# TripleAttenumixer.net
KiCad netlist of a schematic drawn in EAGLE
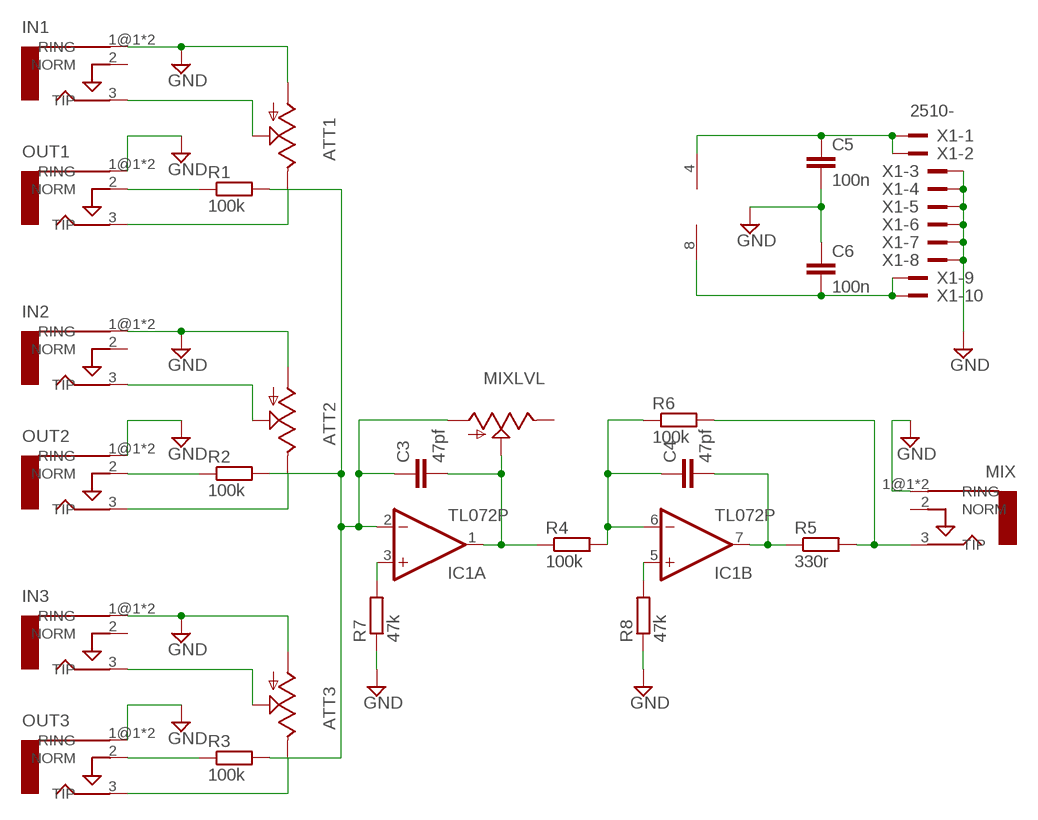
[diagram p0: schematic, sheet 1]

(export (version "E")
  (design (tool "Eeschema 10.0.6"))
  (components
    (comp (ref "ATT1")
      (value "US-EVUF2A")
      (footprint "eagle-import:EVUF")
      (libsource (lib "eagle-import") (part "US-EVUAF2"))
    )
    (comp (ref "ATT2")
      (value "US-EVUF2A")
      (footprint "eagle-import:EVUF")
      (libsource (lib "eagle-import") (part "US-EVUAF2"))
    )
    (comp (ref "ATT3")
      (value "US-EVUF2A")
      (footprint "eagle-import:EVUF")
      (libsource (lib "eagle-import") (part "US-EVUAF2"))
    )
    (comp (ref "C3")
      (value "47pf")
      (footprint "eagle-import:C025_050-025X075")
      (libsource (lib "eagle-import") (part "C-EU025_050-025X075"))
    )
    (comp (ref "C4")
      (value "47pf")
      (footprint "eagle-import:C025_050-025X075")
      (libsource (lib "eagle-import") (part "C-EU025_050-025X075"))
    )
    (comp (ref "C5")
      (value "100n")
      (footprint "eagle-import:C025_050-025X075")
      (fields (field (name "MF") "COOPER BUSSMANN") (field (name "MPN") "100NHG000B"))
      (libsource (lib "eagle-import") (part "C-EU025_050-025X075"))
    )
    (comp (ref "C6")
      (value "100n")
      (footprint "eagle-import:C025_050-025X075")
      (fields (field (name "MF") "COOPER BUSSMANN") (field (name "MPN") "100NHG000B"))
      (libsource (lib "eagle-import") (part "C-EU025_050-025X075"))
    )
    (comp (ref "IC1")
      (value "TL072P")
      (footprint "eagle-import:DIL08")
      (fields (field (name "OC_FARNELL") "unknown"))
      (libsource (lib "eagle-import") (part "TL072P"))
    )
    (comp (ref "IN1")
      (value "AUDIO-JACKERTHENVAR")
      (footprint "eagle-import:ERTHENVAR-JACK")
      (libsource (lib "eagle-import") (part "AUDIO-JACKERTHENVAR"))
    )
    (comp (ref "IN2")
      (value "AUDIO-JACKERTHENVAR")
      (footprint "eagle-import:ERTHENVAR-JACK")
      (libsource (lib "eagle-import") (part "AUDIO-JACKERTHENVAR"))
    )
    (comp (ref "IN3")
      (value "AUDIO-JACKERTHENVAR")
      (footprint "eagle-import:ERTHENVAR-JACK")
      (libsource (lib "eagle-import") (part "AUDIO-JACKERTHENVAR"))
    )
    (comp (ref "MIX")
      (value "AUDIO-JACKERTHENVAR")
      (footprint "eagle-import:ERTHENVAR-JACK")
      (libsource (lib "eagle-import") (part "AUDIO-JACKERTHENVAR"))
    )
    (comp (ref "MIXLVL")
      (value "US-EVUF2A")
      (footprint "eagle-import:EVUF")
      (libsource (lib "eagle-import") (part "US-EVUAF2"))
    )
    (comp (ref "OUT1")
      (value "AUDIO-JACKERTHENVAR")
      (footprint "eagle-import:ERTHENVAR-JACK")
      (libsource (lib "eagle-import") (part "AUDIO-JACKERTHENVAR"))
    )
    (comp (ref "OUT2")
      (value "AUDIO-JACKERTHENVAR")
      (footprint "eagle-import:ERTHENVAR-JACK")
      (libsource (lib "eagle-import") (part "AUDIO-JACKERTHENVAR"))
    )
    (comp (ref "OUT3")
      (value "AUDIO-JACKERTHENVAR")
      (footprint "eagle-import:ERTHENVAR-JACK")
      (libsource (lib "eagle-import") (part "AUDIO-JACKERTHENVAR"))
    )
    (comp (ref "R1")
      (value "100k")
      (footprint "eagle-import:0207_7")
      (libsource (lib "eagle-import") (part "R-EU_0207/7"))
    )
    (comp (ref "R2")
      (value "100k")
      (footprint "eagle-import:0207_7")
      (libsource (lib "eagle-import") (part "R-EU_0207/7"))
    )
    (comp (ref "R3")
      (value "100k")
      (footprint "eagle-import:0207_7")
      (libsource (lib "eagle-import") (part "R-EU_0207/7"))
    )
    (comp (ref "R4")
      (value "100k")
      (footprint "eagle-import:0207_7")
      (libsource (lib "eagle-import") (part "R-EU_0207/7"))
    )
    (comp (ref "R5")
      (value "330r")
      (footprint "eagle-import:0207_7")
      (libsource (lib "eagle-import") (part "R-EU_0207/7"))
    )
    (comp (ref "R6")
      (value "100k")
      (footprint "eagle-import:0207_7")
      (libsource (lib "eagle-import") (part "R-EU_0207/7"))
    )
    (comp (ref "R7")
      (value "47k")
      (footprint "eagle-import:0207_7")
      (libsource (lib "eagle-import") (part "R-EU_0207/7"))
    )
    (comp (ref "R8")
      (value "47k")
      (footprint "eagle-import:0207_7")
      (libsource (lib "eagle-import") (part "R-EU_0207/7"))
    )
    (comp (ref "X1")
      (value "2510-")
      (footprint "eagle-import:PAK100_2500-10")
      (fields
        (field (name "MF") "3M")
        (field (name "MPN") "2510-6002UB")
        (field (name "MPN_1") "N2510-6002RB.")
      )
      (libsource (lib "eagle-import") (part "2510-"))
    )
  )
  (nets
    (net (code "1") (name "GND") (class "Default")
      (node (ref "ATT1") (pin "1") (pinfunction "A_1") (pintype "passive"))
      (node (ref "ATT2") (pin "1") (pinfunction "A_1") (pintype "passive"))
      (node (ref "ATT3") (pin "1") (pinfunction "A_1") (pintype "passive"))
      (node (ref "C5") (pin "2") (pinfunction "2_2") (pintype "passive"))
      (node (ref "C6") (pin "1") (pinfunction "1_1") (pintype "passive"))
      (node (ref "IN1") (pin "1@1") (pinfunction "RING_1@1") (pintype "bidirectional"))
      (node (ref "IN1") (pin "1@2") (pinfunction "RING_1@2") (pintype "bidirectional"))
      (node (ref "IN2") (pin "1@1") (pinfunction "RING_1@1") (pintype "bidirectional"))
      (node (ref "IN2") (pin "1@2") (pinfunction "RING_1@2") (pintype "bidirectional"))
      (node (ref "IN3") (pin "1@1") (pinfunction "RING_1@1") (pintype "bidirectional"))
      (node (ref "IN3") (pin "1@2") (pinfunction "RING_1@2") (pintype "bidirectional"))
      (node (ref "MIX") (pin "1@1") (pinfunction "RING_1@1") (pintype "bidirectional"))
      (node (ref "MIX") (pin "1@2") (pinfunction "RING_1@2") (pintype "bidirectional"))
      (node (ref "OUT1") (pin "1@1") (pinfunction "RING_1@1") (pintype "bidirectional"))
      (node (ref "OUT1") (pin "1@2") (pinfunction "RING_1@2") (pintype "bidirectional"))
      (node (ref "OUT2") (pin "1@1") (pinfunction "RING_1@1") (pintype "bidirectional"))
      (node (ref "OUT2") (pin "1@2") (pinfunction "RING_1@2") (pintype "bidirectional"))
      (node (ref "OUT3") (pin "1@1") (pinfunction "RING_1@1") (pintype "bidirectional"))
      (node (ref "OUT3") (pin "1@2") (pinfunction "RING_1@2") (pintype "bidirectional"))
      (node (ref "R7") (pin "1") (pinfunction "1_1") (pintype "passive"))
      (node (ref "R8") (pin "1") (pinfunction "1_1") (pintype "passive"))
      (node (ref "X1") (pin "3") (pinfunction "KL_3") (pintype "passive"))
      (node (ref "X1") (pin "4") (pinfunction "KL_4") (pintype "passive"))
      (node (ref "X1") (pin "5") (pinfunction "KL_5") (pintype "passive"))
      (node (ref "X1") (pin "6") (pinfunction "KL_6") (pintype "passive"))
      (node (ref "X1") (pin "7") (pinfunction "KL_7") (pintype "passive"))
      (node (ref "X1") (pin "8") (pinfunction "KL_8") (pintype "passive"))
    )
    (net (code "2") (name "Net-(ATT1-E)") (class "Default")
      (node (ref "ATT1") (pin "3") (pinfunction "E_3") (pintype "passive"))
      (node (ref "OUT1") (pin "3") (pinfunction "TIP_3") (pintype "bidirectional"))
    )
    (net (code "3") (name "Net-(ATT1-S)") (class "Default")
      (node (ref "ATT1") (pin "2") (pinfunction "S_2") (pintype "passive"))
      (node (ref "IN1") (pin "3") (pinfunction "TIP_3") (pintype "bidirectional"))
    )
    (net (code "4") (name "Net-(ATT2-E)") (class "Default")
      (node (ref "ATT2") (pin "3") (pinfunction "E_3") (pintype "passive"))
      (node (ref "OUT2") (pin "3") (pinfunction "TIP_3") (pintype "bidirectional"))
    )
    (net (code "5") (name "Net-(ATT2-S)") (class "Default")
      (node (ref "ATT2") (pin "2") (pinfunction "S_2") (pintype "passive"))
      (node (ref "IN2") (pin "3") (pinfunction "TIP_3") (pintype "bidirectional"))
    )
    (net (code "6") (name "Net-(ATT3-E)") (class "Default")
      (node (ref "ATT3") (pin "3") (pinfunction "E_3") (pintype "passive"))
      (node (ref "OUT3") (pin "3") (pinfunction "TIP_3") (pintype "bidirectional"))
    )
    (net (code "7") (name "Net-(ATT3-S)") (class "Default")
      (node (ref "ATT3") (pin "2") (pinfunction "S_2") (pintype "passive"))
      (node (ref "IN3") (pin "3") (pinfunction "TIP_3") (pintype "bidirectional"))
    )
    (net (code "8") (name "Net-(IC1A-+IN)") (class "Default")
      (node (ref "IC1") (pin "3") (pinfunction "+IN_3") (pintype "input"))
      (node (ref "R7") (pin "2") (pinfunction "2_2") (pintype "passive"))
    )
    (net (code "9") (name "Net-(IC1A--IN)") (class "Default")
      (node (ref "C3") (pin "1") (pinfunction "1_1") (pintype "passive"))
      (node (ref "IC1") (pin "2") (pinfunction "-IN_2") (pintype "input"))
      (node (ref "MIXLVL") (pin "1") (pinfunction "A_1") (pintype "passive"))
      (node (ref "R1") (pin "2") (pinfunction "2_2") (pintype "passive"))
      (node (ref "R2") (pin "2") (pinfunction "2_2") (pintype "passive"))
      (node (ref "R3") (pin "2") (pinfunction "2_2") (pintype "passive"))
    )
    (net (code "10") (name "Net-(IC1A-OUT)") (class "Default")
      (node (ref "C3") (pin "2") (pinfunction "2_2") (pintype "passive"))
      (node (ref "IC1") (pin "1") (pinfunction "OUT_1") (pintype "output"))
      (node (ref "MIXLVL") (pin "2") (pinfunction "S_2") (pintype "passive"))
      (node (ref "R4") (pin "1") (pinfunction "1_1") (pintype "passive"))
    )
    (net (code "11") (name "Net-(IC1B-+IN)") (class "Default")
      (node (ref "IC1") (pin "5") (pinfunction "+IN_5") (pintype "input"))
      (node (ref "R8") (pin "2") (pinfunction "2_2") (pintype "passive"))
    )
    (net (code "12") (name "Net-(IC1B--IN)") (class "Default")
      (node (ref "C4") (pin "1") (pinfunction "1_1") (pintype "passive"))
      (node (ref "IC1") (pin "6") (pinfunction "-IN_6") (pintype "input"))
      (node (ref "R4") (pin "2") (pinfunction "2_2") (pintype "passive"))
      (node (ref "R6") (pin "1") (pinfunction "1_1") (pintype "passive"))
    )
    (net (code "13") (name "Net-(IC1B-OUT)") (class "Default")
      (node (ref "C4") (pin "2") (pinfunction "2_2") (pintype "passive"))
      (node (ref "IC1") (pin "7") (pinfunction "OUT_7") (pintype "output"))
      (node (ref "R5") (pin "1") (pinfunction "1_1") (pintype "passive"))
    )
    (net (code "14") (name "Net-(IC1C-V+)") (class "Default")
      (node (ref "C6") (pin "2") (pinfunction "2_2") (pintype "passive"))
      (node (ref "IC1") (pin "8") (pinfunction "V+_8") (pintype "power_in"))
      (node (ref "X1") (pin "10") (pinfunction "KL_10") (pintype "passive"))
      (node (ref "X1") (pin "9") (pinfunction "KL_9") (pintype "passive"))
    )
    (net (code "15") (name "Net-(IC1C-V-)") (class "Default")
      (node (ref "C5") (pin "1") (pinfunction "1_1") (pintype "passive"))
      (node (ref "IC1") (pin "4") (pinfunction "V-_4") (pintype "power_in"))
      (node (ref "X1") (pin "1") (pinfunction "KL_1") (pintype "passive"))
      (node (ref "X1") (pin "2") (pinfunction "KL_2") (pintype "passive"))
    )
    (net (code "16") (name "Net-(MIX-TIP)") (class "Default")
      (node (ref "MIX") (pin "3") (pinfunction "TIP_3") (pintype "bidirectional"))
      (node (ref "R5") (pin "2") (pinfunction "2_2") (pintype "passive"))
      (node (ref "R6") (pin "2") (pinfunction "2_2") (pintype "passive"))
    )
    (net (code "17") (name "Net-(OUT1-NORM)") (class "Default")
      (node (ref "OUT1") (pin "2") (pinfunction "NORM_2") (pintype "bidirectional"))
      (node (ref "R1") (pin "1") (pinfunction "1_1") (pintype "passive"))
    )
    (net (code "18") (name "Net-(OUT2-NORM)") (class "Default")
      (node (ref "OUT2") (pin "2") (pinfunction "NORM_2") (pintype "bidirectional"))
      (node (ref "R2") (pin "1") (pinfunction "1_1") (pintype "passive"))
    )
    (net (code "19") (name "Net-(OUT3-NORM)") (class "Default")
      (node (ref "OUT3") (pin "2") (pinfunction "NORM_2") (pintype "bidirectional"))
      (node (ref "R3") (pin "1") (pinfunction "1_1") (pintype "passive"))
    )
    (net (code "20") (name "unconnected-(IN1-NORM-Pad2)") (class "Default")
      (node (ref "IN1") (pin "2") (pinfunction "NORM_2") (pintype "bidirectional"))
    )
    (net (code "21") (name "unconnected-(IN2-NORM-Pad2)") (class "Default")
      (node (ref "IN2") (pin "2") (pinfunction "NORM_2") (pintype "bidirectional"))
    )
    (net (code "22") (name "unconnected-(IN3-NORM-Pad2)") (class "Default")
      (node (ref "IN3") (pin "2") (pinfunction "NORM_2") (pintype "bidirectional"))
    )
    (net (code "23") (name "unconnected-(MIX-NORM-Pad2)") (class "Default")
      (node (ref "MIX") (pin "2") (pinfunction "NORM_2") (pintype "bidirectional"))
    )
    (net (code "24") (name "unconnected-(MIXLVL-E-Pad3)") (class "Default")
      (node (ref "MIXLVL") (pin "3") (pinfunction "E_3") (pintype "passive"))
    )
  )
)
